# Dual_Half_Bridge_With_LDO_Regulator_DRV8.net
KiCad netlist of a schematic drawn in EAGLE
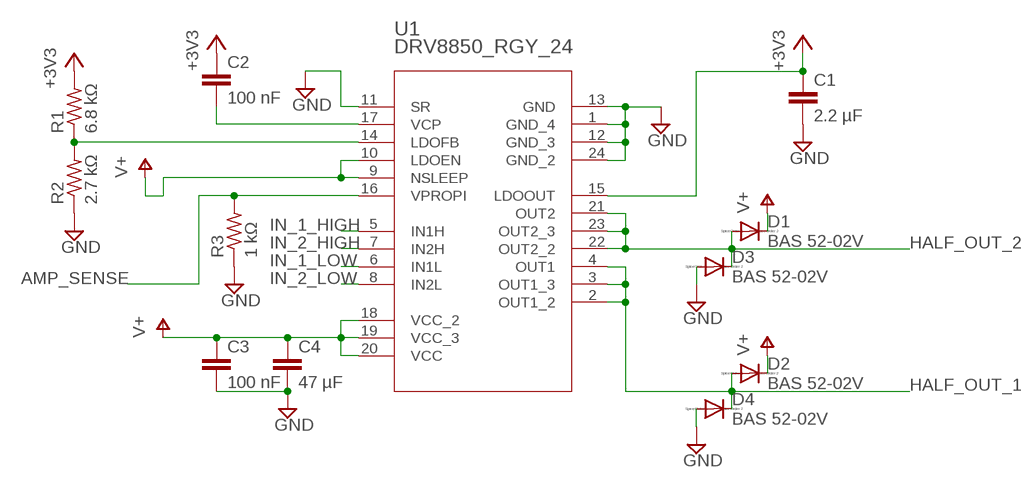
[diagram p0: schematic, sheet 1]

(export (version "E")
  (design (tool "Eeschema 10.0.6"))
  (components
    (comp (ref "C1")
      (value "2.2 µF")
      (footprint "eagle-import:C0603")
      (libsource (lib "eagle-import") (part "C-EUC0603"))
    )
    (comp (ref "C2")
      (value "100 nF")
      (footprint "eagle-import:C0402")
      (libsource (lib "eagle-import") (part "C-EUC0402"))
    )
    (comp (ref "C3")
      (value "100 nF")
      (footprint "eagle-import:C0402")
      (libsource (lib "eagle-import") (part "C-EUC0402"))
    )
    (comp (ref "C4")
      (value "47 µF")
      (footprint "eagle-import:C0805")
      (libsource (lib "eagle-import") (part "C-EUC0805"))
    )
    (comp (ref "D1")
      (value "BAS 52-02V")
      (footprint "eagle-import:SOD523")
      (libsource (lib "eagle-import") (part "DIODE-SOD523"))
    )
    (comp (ref "D2")
      (value "BAS 52-02V")
      (footprint "eagle-import:SOD523")
      (libsource (lib "eagle-import") (part "DIODE-SOD523"))
    )
    (comp (ref "D3")
      (value "BAS 52-02V")
      (footprint "eagle-import:SOD523")
      (libsource (lib "eagle-import") (part "DIODE-SOD523"))
    )
    (comp (ref "D4")
      (value "BAS 52-02V")
      (footprint "eagle-import:SOD523")
      (libsource (lib "eagle-import") (part "DIODE-SOD523"))
    )
    (comp (ref "R1")
      (value "6.8 kΩ")
      (footprint "eagle-import:R0402")
      (libsource (lib "eagle-import") (part "R-US_R0402"))
    )
    (comp (ref "R2")
      (value "2.7 kΩ")
      (footprint "eagle-import:R0402")
      (libsource (lib "eagle-import") (part "R-US_R0402"))
    )
    (comp (ref "R3")
      (value "1 kΩ")
      (footprint "eagle-import:R0402")
      (libsource (lib "eagle-import") (part "R-US_R0402"))
    )
    (comp (ref "U1")
      (value "DRV8850_RGY_24")
      (footprint "eagle-import:RGY_24")
      (fields (field (name "MANUFACTURER_PART_NUMBER") "drv8850_rgy_24"))
      (libsource (lib "eagle-import") (part "DRV8850_RGY_24"))
    )
  )
  (nets
    (net (code "1") (name "+3V3") (class "Default")
      (node (ref "C1") (pin "1") (pinfunction "1_1") (pintype "passive"))
      (node (ref "C2") (pin "1") (pinfunction "1_1") (pintype "passive"))
      (node (ref "R1") (pin "2") (pinfunction "2_2") (pintype "passive"))
      (node (ref "U1") (pin "15") (pinfunction "LDOOUT_15") (pintype "output"))
    )
    (net (code "2") (name "/AMP_SENSE") (class "Default")
      (node (ref "R3") (pin "2") (pinfunction "2_2") (pintype "passive"))
      (node (ref "U1") (pin "16") (pinfunction "VPROPI_16") (pintype "output"))
    )
    (net (code "3") (name "/HALF_OUT_1") (class "Default")
      (node (ref "D2") (pin "A") (pinfunction "A_A") (pintype "passive"))
      (node (ref "D4") (pin "C") (pinfunction "C_C") (pintype "passive"))
      (node (ref "U1") (pin "2") (pinfunction "OUT1_2_2") (pintype "output"))
      (node (ref "U1") (pin "3") (pinfunction "OUT1_3_3") (pintype "output"))
      (node (ref "U1") (pin "4") (pinfunction "OUT1_4") (pintype "output"))
    )
    (net (code "4") (name "/HALF_OUT_2") (class "Default")
      (node (ref "D1") (pin "A") (pinfunction "A_A") (pintype "passive"))
      (node (ref "D3") (pin "C") (pinfunction "C_C") (pintype "passive"))
      (node (ref "U1") (pin "21") (pinfunction "OUT2_21") (pintype "output"))
      (node (ref "U1") (pin "22") (pinfunction "OUT2_2_22") (pintype "output"))
      (node (ref "U1") (pin "23") (pinfunction "OUT2_3_23") (pintype "output"))
    )
    (net (code "5") (name "/IN_1_HIGH") (class "Default")
      (node (ref "U1") (pin "5") (pinfunction "IN1H_5") (pintype "input"))
    )
    (net (code "6") (name "/IN_1_LOW") (class "Default")
      (node (ref "U1") (pin "6") (pinfunction "IN1L_6") (pintype "input"))
    )
    (net (code "7") (name "/IN_2_HIGH") (class "Default")
      (node (ref "U1") (pin "7") (pinfunction "IN2H_7") (pintype "input"))
    )
    (net (code "8") (name "/IN_2_LOW") (class "Default")
      (node (ref "U1") (pin "8") (pinfunction "IN2L_8") (pintype "input"))
    )
    (net (code "9") (name "GND") (class "Default")
      (node (ref "C1") (pin "2") (pinfunction "2_2") (pintype "passive"))
      (node (ref "C3") (pin "2") (pinfunction "2_2") (pintype "passive"))
      (node (ref "C4") (pin "2") (pinfunction "2_2") (pintype "passive"))
      (node (ref "D3") (pin "A") (pinfunction "A_A") (pintype "passive"))
      (node (ref "D4") (pin "A") (pinfunction "A_A") (pintype "passive"))
      (node (ref "R2") (pin "1") (pinfunction "1_1") (pintype "passive"))
      (node (ref "R3") (pin "1") (pinfunction "1_1") (pintype "passive"))
      (node (ref "U1") (pin "1") (pinfunction "GND_4_1") (pintype "power_in"))
      (node (ref "U1") (pin "11") (pinfunction "SR_11") (pintype "bidirectional"))
      (node (ref "U1") (pin "12") (pinfunction "GND_3_12") (pintype "power_in"))
      (node (ref "U1") (pin "13") (pinfunction "GND_13") (pintype "power_in"))
      (node (ref "U1") (pin "24") (pinfunction "GND_2_24") (pintype "power_in"))
    )
    (net (code "10") (name "Net-(U1-LDOFB)") (class "Default")
      (node (ref "R1") (pin "1") (pinfunction "1_1") (pintype "passive"))
      (node (ref "R2") (pin "2") (pinfunction "2_2") (pintype "passive"))
      (node (ref "U1") (pin "14") (pinfunction "LDOFB_14") (pintype "input"))
    )
    (net (code "11") (name "Net-(U1-VCP)") (class "Default")
      (node (ref "C2") (pin "2") (pinfunction "2_2") (pintype "passive"))
      (node (ref "U1") (pin "17") (pinfunction "VCP_17") (pintype "passive"))
    )
    (net (code "12") (name "V+") (class "Default")
      (node (ref "C3") (pin "1") (pinfunction "1_1") (pintype "passive"))
      (node (ref "C4") (pin "1") (pinfunction "1_1") (pintype "passive"))
      (node (ref "D1") (pin "C") (pinfunction "C_C") (pintype "passive"))
      (node (ref "D2") (pin "C") (pinfunction "C_C") (pintype "passive"))
      (node (ref "U1") (pin "10") (pinfunction "LDOEN_10") (pintype "input"))
      (node (ref "U1") (pin "18") (pinfunction "VCC_2_18") (pintype "power_in"))
      (node (ref "U1") (pin "19") (pinfunction "VCC_3_19") (pintype "power_in"))
      (node (ref "U1") (pin "20") (pinfunction "VCC_20") (pintype "power_in"))
      (node (ref "U1") (pin "9") (pinfunction "NSLEEP_9") (pintype "input"))
    )
  )
)
